# hand.net
KiCad netlist of a schematic drawn in EAGLE
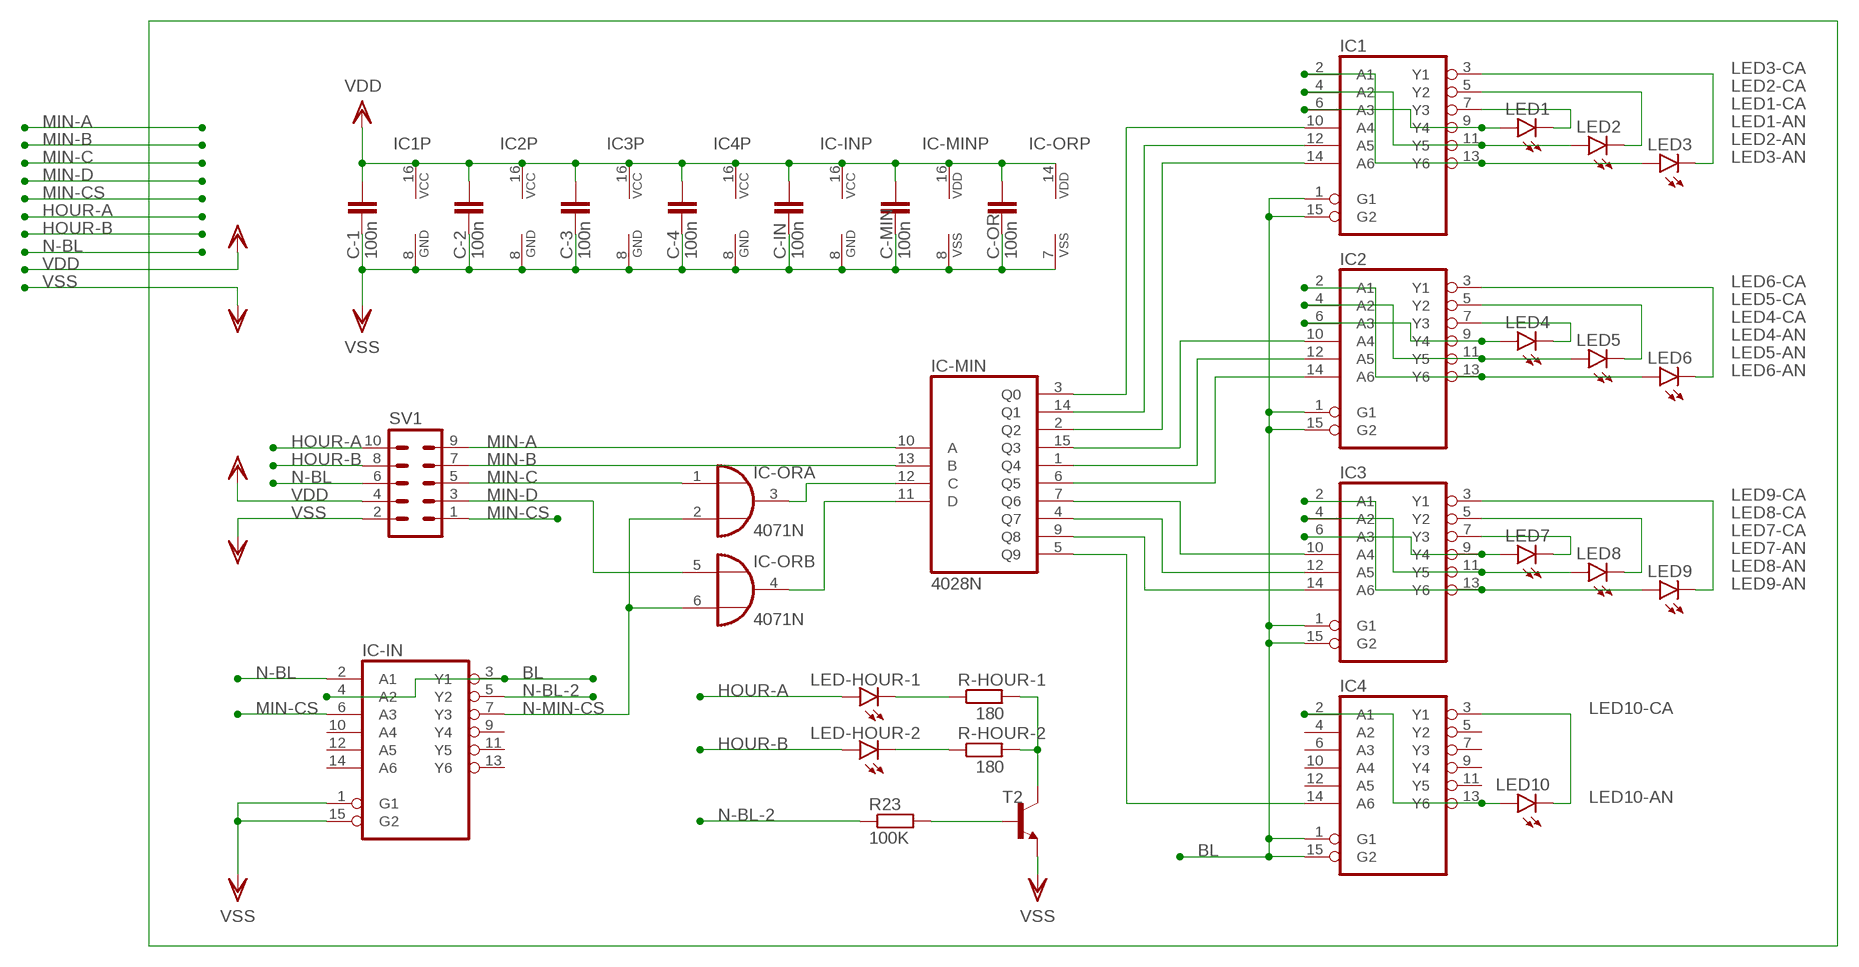
[diagram p0: schematic, sheet 1]

(export (version "E")
  (design (tool "Eeschema 10.0.6"))
  (components
    (comp (ref "C-1")
      (value "100n")
      (footprint "eagle-import:C050-025X075")
      (libsource (lib "eagle-import") (part "C-EU050-025X075"))
    )
    (comp (ref "C-2")
      (value "100n")
      (footprint "eagle-import:C050-025X075")
      (libsource (lib "eagle-import") (part "C-EU050-025X075"))
    )
    (comp (ref "C-3")
      (value "100n")
      (footprint "eagle-import:C050-025X075")
      (libsource (lib "eagle-import") (part "C-EU050-025X075"))
    )
    (comp (ref "C-4")
      (value "100n")
      (footprint "eagle-import:C050-025X075")
      (libsource (lib "eagle-import") (part "C-EU050-025X075"))
    )
    (comp (ref "C-IN")
      (value "100n")
      (footprint "eagle-import:C050-025X075")
      (libsource (lib "eagle-import") (part "C-EU050-025X075"))
    )
    (comp (ref "C-MIN")
      (value "100n")
      (footprint "eagle-import:C050-025X075")
      (libsource (lib "eagle-import") (part "C-EU050-025X075"))
    )
    (comp (ref "C-OR")
      (value "100n")
      (footprint "eagle-import:C050-025X075")
      (libsource (lib "eagle-import") (part "C-EU050-025X075"))
    )
    (comp (ref "IC-IN")
      (value "74HC366N")
      (footprint "eagle-import:DIL16")
      (libsource (lib "eagle-import") (part "74366NHC"))
    )
    (comp (ref "IC-MIN")
      (value "4028N")
      (footprint "eagle-import:DIL16")
      (libsource (lib "eagle-import") (part "4028N"))
    )
    (comp (ref "IC-OR")
      (value "4071N")
      (footprint "eagle-import:DIL14")
      (libsource (lib "eagle-import") (part "4071N"))
    )
    (comp (ref "IC1")
      (value "74HC366N")
      (footprint "eagle-import:DIL16")
      (libsource (lib "eagle-import") (part "74366NHC"))
    )
    (comp (ref "IC2")
      (value "74HC366N")
      (footprint "eagle-import:DIL16")
      (libsource (lib "eagle-import") (part "74366NHC"))
    )
    (comp (ref "IC3")
      (value "74HC366N")
      (footprint "eagle-import:DIL16")
      (libsource (lib "eagle-import") (part "74366NHC"))
    )
    (comp (ref "IC4")
      (value "74HC366N")
      (footprint "eagle-import:DIL16")
      (libsource (lib "eagle-import") (part "74366NHC"))
    )
    (comp (ref "LED-HOUR-1")
      (value "LED10MM")
      (footprint "eagle-import:LED10MM")
      (libsource (lib "eagle-import") (part "LED10MM"))
    )
    (comp (ref "LED-HOUR-2")
      (value "LED10MM")
      (footprint "eagle-import:LED10MM")
      (libsource (lib "eagle-import") (part "LED10MM"))
    )
    (comp (ref "LED1")
      (value "LED5MM")
      (footprint "eagle-import:LED5MM")
      (libsource (lib "eagle-import") (part "LED5MM"))
    )
    (comp (ref "LED2")
      (value "LED5MM")
      (footprint "eagle-import:LED5MM")
      (libsource (lib "eagle-import") (part "LED5MM"))
    )
    (comp (ref "LED3")
      (value "LED5MM")
      (footprint "eagle-import:LED5MM")
      (libsource (lib "eagle-import") (part "LED5MM"))
    )
    (comp (ref "LED4")
      (value "LED5MM")
      (footprint "eagle-import:LED5MM")
      (libsource (lib "eagle-import") (part "LED5MM"))
    )
    (comp (ref "LED5")
      (value "LED5MM")
      (footprint "eagle-import:LED5MM")
      (libsource (lib "eagle-import") (part "LED5MM"))
    )
    (comp (ref "LED6")
      (value "LED5MM")
      (footprint "eagle-import:LED5MM")
      (libsource (lib "eagle-import") (part "LED5MM"))
    )
    (comp (ref "LED7")
      (value "LED5MM")
      (footprint "eagle-import:LED5MM")
      (libsource (lib "eagle-import") (part "LED5MM"))
    )
    (comp (ref "LED8")
      (value "LED5MM")
      (footprint "eagle-import:LED5MM")
      (libsource (lib "eagle-import") (part "LED5MM"))
    )
    (comp (ref "LED9")
      (value "LED5MM")
      (footprint "eagle-import:LED5MM")
      (libsource (lib "eagle-import") (part "LED5MM"))
    )
    (comp (ref "LED10")
      (value "LED5MM")
      (footprint "eagle-import:LED5MM")
      (libsource (lib "eagle-import") (part "LED5MM"))
    )
    (comp (ref "R-HOUR-1")
      (value "180")
      (footprint "eagle-import:0207_10")
      (libsource (lib "eagle-import") (part "R-EU_0207/10"))
    )
    (comp (ref "R-HOUR-2")
      (value "180")
      (footprint "eagle-import:0207_10")
      (libsource (lib "eagle-import") (part "R-EU_0207/10"))
    )
    (comp (ref "R23")
      (value "100K")
      (footprint "eagle-import:0207_10")
      (libsource (lib "eagle-import") (part "R-EU_0207/10"))
    )
    (comp (ref "SV1")
      (value "ML10")
      (footprint "eagle-import:ML10")
      (libsource (lib "eagle-import") (part "ML10"))
    )
    (comp (ref "T2")
      (value "BC547-NPN-TO92-CBE")
      (footprint "eagle-import:TO92-CBE")
      (libsource (lib "eagle-import") (part "-NPN-TO92-CBEBC547"))
    )
  )
  (nets
    (net (code "1") (name "/BL") (class "Default")
      (node (ref "IC-IN") (pin "3") (pinfunction "Y1_3") (pintype "tri_state"))
      (node (ref "IC-IN") (pin "4") (pinfunction "A2_4") (pintype "input"))
      (node (ref "IC1") (pin "1") (pinfunction "G1_1") (pintype "input"))
      (node (ref "IC1") (pin "15") (pinfunction "G2_15") (pintype "input"))
      (node (ref "IC2") (pin "1") (pinfunction "G1_1") (pintype "input"))
      (node (ref "IC2") (pin "15") (pinfunction "G2_15") (pintype "input"))
      (node (ref "IC3") (pin "1") (pinfunction "G1_1") (pintype "input"))
      (node (ref "IC3") (pin "15") (pinfunction "G2_15") (pintype "input"))
      (node (ref "IC4") (pin "1") (pinfunction "G1_1") (pintype "input"))
      (node (ref "IC4") (pin "15") (pinfunction "G2_15") (pintype "input"))
    )
    (net (code "2") (name "/HOUR-A") (class "Default")
      (node (ref "LED-HOUR-1") (pin "A") (pinfunction "A_A") (pintype "passive"))
      (node (ref "SV1") (pin "10") (pinfunction "10_10") (pintype "passive"))
    )
    (net (code "3") (name "/HOUR-B") (class "Default")
      (node (ref "LED-HOUR-2") (pin "A") (pinfunction "A_A") (pintype "passive"))
      (node (ref "SV1") (pin "8") (pinfunction "8_8") (pintype "passive"))
    )
    (net (code "4") (name "/LED1-AN") (class "Default")
      (node (ref "IC1") (pin "6") (pinfunction "A3_6") (pintype "input"))
      (node (ref "IC1") (pin "9") (pinfunction "Y4_9") (pintype "tri_state"))
      (node (ref "LED1") (pin "A") (pinfunction "A_A") (pintype "passive"))
    )
    (net (code "5") (name "/LED1-CA") (class "Default")
      (node (ref "IC1") (pin "7") (pinfunction "Y3_7") (pintype "tri_state"))
      (node (ref "LED1") (pin "K") (pinfunction "C_K") (pintype "passive"))
    )
    (net (code "6") (name "/LED2-AN") (class "Default")
      (node (ref "IC1") (pin "11") (pinfunction "Y5_11") (pintype "tri_state"))
      (node (ref "IC1") (pin "4") (pinfunction "A2_4") (pintype "input"))
      (node (ref "LED2") (pin "A") (pinfunction "A_A") (pintype "passive"))
    )
    (net (code "7") (name "/LED2-CA") (class "Default")
      (node (ref "IC1") (pin "5") (pinfunction "Y2_5") (pintype "tri_state"))
      (node (ref "LED2") (pin "K") (pinfunction "C_K") (pintype "passive"))
    )
    (net (code "8") (name "/LED3-AN") (class "Default")
      (node (ref "IC1") (pin "13") (pinfunction "Y6_13") (pintype "tri_state"))
      (node (ref "IC1") (pin "2") (pinfunction "A1_2") (pintype "input"))
      (node (ref "LED3") (pin "A") (pinfunction "A_A") (pintype "passive"))
    )
    (net (code "9") (name "/LED3-CA") (class "Default")
      (node (ref "IC1") (pin "3") (pinfunction "Y1_3") (pintype "tri_state"))
      (node (ref "LED3") (pin "K") (pinfunction "C_K") (pintype "passive"))
    )
    (net (code "10") (name "/LED4-AN") (class "Default")
      (node (ref "IC2") (pin "6") (pinfunction "A3_6") (pintype "input"))
      (node (ref "IC2") (pin "9") (pinfunction "Y4_9") (pintype "tri_state"))
      (node (ref "LED4") (pin "A") (pinfunction "A_A") (pintype "passive"))
    )
    (net (code "11") (name "/LED4-CA") (class "Default")
      (node (ref "IC2") (pin "7") (pinfunction "Y3_7") (pintype "tri_state"))
      (node (ref "LED4") (pin "K") (pinfunction "C_K") (pintype "passive"))
    )
    (net (code "12") (name "/LED5-AN") (class "Default")
      (node (ref "IC2") (pin "11") (pinfunction "Y5_11") (pintype "tri_state"))
      (node (ref "IC2") (pin "4") (pinfunction "A2_4") (pintype "input"))
      (node (ref "LED5") (pin "A") (pinfunction "A_A") (pintype "passive"))
    )
    (net (code "13") (name "/LED5-CA") (class "Default")
      (node (ref "IC2") (pin "5") (pinfunction "Y2_5") (pintype "tri_state"))
      (node (ref "LED5") (pin "K") (pinfunction "C_K") (pintype "passive"))
    )
    (net (code "14") (name "/LED6-AN") (class "Default")
      (node (ref "IC2") (pin "13") (pinfunction "Y6_13") (pintype "tri_state"))
      (node (ref "IC2") (pin "2") (pinfunction "A1_2") (pintype "input"))
      (node (ref "LED6") (pin "A") (pinfunction "A_A") (pintype "passive"))
    )
    (net (code "15") (name "/LED6-CA") (class "Default")
      (node (ref "IC2") (pin "3") (pinfunction "Y1_3") (pintype "tri_state"))
      (node (ref "LED6") (pin "K") (pinfunction "C_K") (pintype "passive"))
    )
    (net (code "16") (name "/LED7-AN") (class "Default")
      (node (ref "IC3") (pin "6") (pinfunction "A3_6") (pintype "input"))
      (node (ref "IC3") (pin "9") (pinfunction "Y4_9") (pintype "tri_state"))
      (node (ref "LED7") (pin "A") (pinfunction "A_A") (pintype "passive"))
    )
    (net (code "17") (name "/LED7-CA") (class "Default")
      (node (ref "IC3") (pin "7") (pinfunction "Y3_7") (pintype "tri_state"))
      (node (ref "LED7") (pin "K") (pinfunction "C_K") (pintype "passive"))
    )
    (net (code "18") (name "/LED8-AN") (class "Default")
      (node (ref "IC3") (pin "11") (pinfunction "Y5_11") (pintype "tri_state"))
      (node (ref "IC3") (pin "4") (pinfunction "A2_4") (pintype "input"))
      (node (ref "LED8") (pin "A") (pinfunction "A_A") (pintype "passive"))
    )
    (net (code "19") (name "/LED8-CA") (class "Default")
      (node (ref "IC3") (pin "5") (pinfunction "Y2_5") (pintype "tri_state"))
      (node (ref "LED8") (pin "K") (pinfunction "C_K") (pintype "passive"))
    )
    (net (code "20") (name "/LED9-AN") (class "Default")
      (node (ref "IC3") (pin "13") (pinfunction "Y6_13") (pintype "tri_state"))
      (node (ref "IC3") (pin "2") (pinfunction "A1_2") (pintype "input"))
      (node (ref "LED9") (pin "A") (pinfunction "A_A") (pintype "passive"))
    )
    (net (code "21") (name "/LED9-CA") (class "Default")
      (node (ref "IC3") (pin "3") (pinfunction "Y1_3") (pintype "tri_state"))
      (node (ref "LED9") (pin "K") (pinfunction "C_K") (pintype "passive"))
    )
    (net (code "22") (name "/LED10-AN") (class "Default")
      (node (ref "IC4") (pin "13") (pinfunction "Y6_13") (pintype "tri_state"))
      (node (ref "IC4") (pin "2") (pinfunction "A1_2") (pintype "input"))
      (node (ref "LED10") (pin "A") (pinfunction "A_A") (pintype "passive"))
    )
    (net (code "23") (name "/LED10-CA") (class "Default")
      (node (ref "IC4") (pin "3") (pinfunction "Y1_3") (pintype "tri_state"))
      (node (ref "LED10") (pin "K") (pinfunction "C_K") (pintype "passive"))
    )
    (net (code "24") (name "/MIN-A") (class "Default")
      (node (ref "IC-MIN") (pin "10") (pinfunction "A_10") (pintype "input"))
      (node (ref "SV1") (pin "9") (pinfunction "9_9") (pintype "passive"))
    )
    (net (code "25") (name "/MIN-B") (class "Default")
      (node (ref "IC-MIN") (pin "13") (pinfunction "B_13") (pintype "input"))
      (node (ref "SV1") (pin "7") (pinfunction "7_7") (pintype "passive"))
    )
    (net (code "26") (name "/MIN-C") (class "Default")
      (node (ref "IC-OR") (pin "1") (pinfunction "I0_1") (pintype "input"))
      (node (ref "SV1") (pin "5") (pinfunction "5_5") (pintype "passive"))
    )
    (net (code "27") (name "/MIN-CS") (class "Default")
      (node (ref "IC-IN") (pin "6") (pinfunction "A3_6") (pintype "input"))
      (node (ref "SV1") (pin "1") (pinfunction "1_1") (pintype "passive"))
    )
    (net (code "28") (name "/MIN-D") (class "Default")
      (node (ref "IC-OR") (pin "5") (pinfunction "I0_5") (pintype "input"))
      (node (ref "SV1") (pin "3") (pinfunction "3_3") (pintype "passive"))
    )
    (net (code "29") (name "/N-BL") (class "Default")
      (node (ref "IC-IN") (pin "2") (pinfunction "A1_2") (pintype "input"))
      (node (ref "SV1") (pin "6") (pinfunction "6_6") (pintype "passive"))
    )
    (net (code "30") (name "/N-BL-2") (class "Default")
      (node (ref "IC-IN") (pin "5") (pinfunction "Y2_5") (pintype "tri_state"))
      (node (ref "R23") (pin "1") (pinfunction "1_1") (pintype "passive"))
    )
    (net (code "31") (name "/N-MIN-CS") (class "Default")
      (node (ref "IC-IN") (pin "7") (pinfunction "Y3_7") (pintype "tri_state"))
      (node (ref "IC-OR") (pin "2") (pinfunction "I1_2") (pintype "input"))
      (node (ref "IC-OR") (pin "6") (pinfunction "I1_6") (pintype "input"))
    )
    (net (code "32") (name "Net-(IC-MINA-C)") (class "Default")
      (node (ref "IC-MIN") (pin "12") (pinfunction "C_12") (pintype "input"))
      (node (ref "IC-OR") (pin "3") (pinfunction "O_3") (pintype "output"))
    )
    (net (code "33") (name "Net-(IC-MINA-D)") (class "Default")
      (node (ref "IC-MIN") (pin "11") (pinfunction "D_11") (pintype "input"))
      (node (ref "IC-OR") (pin "4") (pinfunction "O_4") (pintype "output"))
    )
    (net (code "34") (name "Net-(IC-MINA-Q0)") (class "Default")
      (node (ref "IC-MIN") (pin "3") (pinfunction "Q0_3") (pintype "output"))
      (node (ref "IC1") (pin "10") (pinfunction "A4_10") (pintype "input"))
    )
    (net (code "35") (name "Net-(IC-MINA-Q1)") (class "Default")
      (node (ref "IC-MIN") (pin "14") (pinfunction "Q1_14") (pintype "output"))
      (node (ref "IC1") (pin "12") (pinfunction "A5_12") (pintype "input"))
    )
    (net (code "36") (name "Net-(IC-MINA-Q2)") (class "Default")
      (node (ref "IC-MIN") (pin "2") (pinfunction "Q2_2") (pintype "output"))
      (node (ref "IC1") (pin "14") (pinfunction "A6_14") (pintype "input"))
    )
    (net (code "37") (name "Net-(IC-MINA-Q3)") (class "Default")
      (node (ref "IC-MIN") (pin "15") (pinfunction "Q3_15") (pintype "output"))
      (node (ref "IC2") (pin "10") (pinfunction "A4_10") (pintype "input"))
    )
    (net (code "38") (name "Net-(IC-MINA-Q4)") (class "Default")
      (node (ref "IC-MIN") (pin "1") (pinfunction "Q4_1") (pintype "output"))
      (node (ref "IC2") (pin "12") (pinfunction "A5_12") (pintype "input"))
    )
    (net (code "39") (name "Net-(IC-MINA-Q5)") (class "Default")
      (node (ref "IC-MIN") (pin "6") (pinfunction "Q5_6") (pintype "output"))
      (node (ref "IC2") (pin "14") (pinfunction "A6_14") (pintype "input"))
    )
    (net (code "40") (name "Net-(IC-MINA-Q6)") (class "Default")
      (node (ref "IC-MIN") (pin "7") (pinfunction "Q6_7") (pintype "output"))
      (node (ref "IC3") (pin "10") (pinfunction "A4_10") (pintype "input"))
    )
    (net (code "41") (name "Net-(IC-MINA-Q7)") (class "Default")
      (node (ref "IC-MIN") (pin "4") (pinfunction "Q7_4") (pintype "output"))
      (node (ref "IC3") (pin "12") (pinfunction "A5_12") (pintype "input"))
    )
    (net (code "42") (name "Net-(IC-MINA-Q8)") (class "Default")
      (node (ref "IC-MIN") (pin "9") (pinfunction "Q8_9") (pintype "output"))
      (node (ref "IC3") (pin "14") (pinfunction "A6_14") (pintype "input"))
    )
    (net (code "43") (name "Net-(IC-MINA-Q9)") (class "Default")
      (node (ref "IC-MIN") (pin "5") (pinfunction "Q9_5") (pintype "output"))
      (node (ref "IC4") (pin "14") (pinfunction "A6_14") (pintype "input"))
    )
    (net (code "44") (name "Net-(LED-HOUR-1-C)") (class "Default")
      (node (ref "LED-HOUR-1") (pin "K") (pinfunction "C_K") (pintype "passive"))
      (node (ref "R-HOUR-1") (pin "1") (pinfunction "1_1") (pintype "passive"))
    )
    (net (code "45") (name "Net-(LED-HOUR-2-C)") (class "Default")
      (node (ref "LED-HOUR-2") (pin "K") (pinfunction "C_K") (pintype "passive"))
      (node (ref "R-HOUR-2") (pin "1") (pinfunction "1_1") (pintype "passive"))
    )
    (net (code "46") (name "Net-(R-HOUR-1-Pad2)") (class "Default")
      (node (ref "R-HOUR-1") (pin "2") (pinfunction "2_2") (pintype "passive"))
      (node (ref "R-HOUR-2") (pin "2") (pinfunction "2_2") (pintype "passive"))
      (node (ref "T2") (pin "C") (pinfunction "C_C") (pintype "passive"))
    )
    (net (code "47") (name "Net-(R23-Pad2)") (class "Default")
      (node (ref "R23") (pin "2") (pinfunction "2_2") (pintype "passive"))
      (node (ref "T2") (pin "B") (pinfunction "B_B") (pintype "passive"))
    )
    (net (code "48") (name "VDD") (class "Default")
      (node (ref "C-1") (pin "1") (pinfunction "1_1") (pintype "passive"))
      (node (ref "C-2") (pin "1") (pinfunction "1_1") (pintype "passive"))
      (node (ref "C-3") (pin "1") (pinfunction "1_1") (pintype "passive"))
      (node (ref "C-4") (pin "1") (pinfunction "1_1") (pintype "passive"))
      (node (ref "C-IN") (pin "1") (pinfunction "1_1") (pintype "passive"))
      (node (ref "C-MIN") (pin "1") (pinfunction "1_1") (pintype "passive"))
      (node (ref "C-OR") (pin "1") (pinfunction "1_1") (pintype "passive"))
      (node (ref "IC-IN") (pin "16") (pinfunction "VCC_16") (pintype "power_in"))
      (node (ref "IC-MIN") (pin "16") (pinfunction "VDD_16") (pintype "power_in"))
      (node (ref "IC-OR") (pin "14") (pinfunction "VDD_14") (pintype "power_in"))
      (node (ref "IC1") (pin "16") (pinfunction "VCC_16") (pintype "power_in"))
      (node (ref "IC2") (pin "16") (pinfunction "VCC_16") (pintype "power_in"))
      (node (ref "IC3") (pin "16") (pinfunction "VCC_16") (pintype "power_in"))
      (node (ref "IC4") (pin "16") (pinfunction "VCC_16") (pintype "power_in"))
      (node (ref "SV1") (pin "4") (pinfunction "4_4") (pintype "passive"))
    )
    (net (code "49") (name "VSS") (class "Default")
      (node (ref "C-1") (pin "2") (pinfunction "2_2") (pintype "passive"))
      (node (ref "C-2") (pin "2") (pinfunction "2_2") (pintype "passive"))
      (node (ref "C-3") (pin "2") (pinfunction "2_2") (pintype "passive"))
      (node (ref "C-4") (pin "2") (pinfunction "2_2") (pintype "passive"))
      (node (ref "C-IN") (pin "2") (pinfunction "2_2") (pintype "passive"))
      (node (ref "C-MIN") (pin "2") (pinfunction "2_2") (pintype "passive"))
      (node (ref "C-OR") (pin "2") (pinfunction "2_2") (pintype "passive"))
      (node (ref "IC-IN") (pin "1") (pinfunction "G1_1") (pintype "input"))
      (node (ref "IC-IN") (pin "15") (pinfunction "G2_15") (pintype "input"))
      (node (ref "IC-IN") (pin "8") (pinfunction "GND_8") (pintype "power_in"))
      (node (ref "IC-MIN") (pin "8") (pinfunction "VSS_8") (pintype "power_in"))
      (node (ref "IC-OR") (pin "7") (pinfunction "VSS_7") (pintype "power_in"))
      (node (ref "IC1") (pin "8") (pinfunction "GND_8") (pintype "power_in"))
      (node (ref "IC2") (pin "8") (pinfunction "GND_8") (pintype "power_in"))
      (node (ref "IC3") (pin "8") (pinfunction "GND_8") (pintype "power_in"))
      (node (ref "IC4") (pin "8") (pinfunction "GND_8") (pintype "power_in"))
      (node (ref "SV1") (pin "2") (pinfunction "2_2") (pintype "passive"))
      (node (ref "T2") (pin "E") (pinfunction "E_E") (pintype "passive"))
    )
    (net (code "50") (name "unconnected-(IC-INA-A4-Pad10)") (class "Default")
      (node (ref "IC-IN") (pin "10") (pinfunction "A4_10") (pintype "input"))
    )
    (net (code "51") (name "unconnected-(IC-INA-A5-Pad12)") (class "Default")
      (node (ref "IC-IN") (pin "12") (pinfunction "A5_12") (pintype "input"))
    )
    (net (code "52") (name "unconnected-(IC-INA-A6-Pad14)") (class "Default")
      (node (ref "IC-IN") (pin "14") (pinfunction "A6_14") (pintype "input"))
    )
    (net (code "53") (name "unconnected-(IC-INA-Y4-Pad9)") (class "Default")
      (node (ref "IC-IN") (pin "9") (pinfunction "Y4_9") (pintype "tri_state"))
    )
    (net (code "54") (name "unconnected-(IC-INA-Y5-Pad11)") (class "Default")
      (node (ref "IC-IN") (pin "11") (pinfunction "Y5_11") (pintype "tri_state"))
    )
    (net (code "55") (name "unconnected-(IC-INA-Y6-Pad13)") (class "Default")
      (node (ref "IC-IN") (pin "13") (pinfunction "Y6_13") (pintype "tri_state"))
    )
    (net (code "56") (name "unconnected-(IC4A-A2-Pad4)") (class "Default")
      (node (ref "IC4") (pin "4") (pinfunction "A2_4") (pintype "input"))
    )
    (net (code "57") (name "unconnected-(IC4A-A3-Pad6)") (class "Default")
      (node (ref "IC4") (pin "6") (pinfunction "A3_6") (pintype "input"))
    )
    (net (code "58") (name "unconnected-(IC4A-A4-Pad10)") (class "Default")
      (node (ref "IC4") (pin "10") (pinfunction "A4_10") (pintype "input"))
    )
    (net (code "59") (name "unconnected-(IC4A-A5-Pad12)") (class "Default")
      (node (ref "IC4") (pin "12") (pinfunction "A5_12") (pintype "input"))
    )
    (net (code "60") (name "unconnected-(IC4A-Y2-Pad5)") (class "Default")
      (node (ref "IC4") (pin "5") (pinfunction "Y2_5") (pintype "tri_state"))
    )
    (net (code "61") (name "unconnected-(IC4A-Y3-Pad7)") (class "Default")
      (node (ref "IC4") (pin "7") (pinfunction "Y3_7") (pintype "tri_state"))
    )
    (net (code "62") (name "unconnected-(IC4A-Y4-Pad9)") (class "Default")
      (node (ref "IC4") (pin "9") (pinfunction "Y4_9") (pintype "tri_state"))
    )
    (net (code "63") (name "unconnected-(IC4A-Y5-Pad11)") (class "Default")
      (node (ref "IC4") (pin "11") (pinfunction "Y5_11") (pintype "tri_state"))
    )
  )
)
